# F200s.net
KiCad netlist of a schematic drawn in Altium Designer
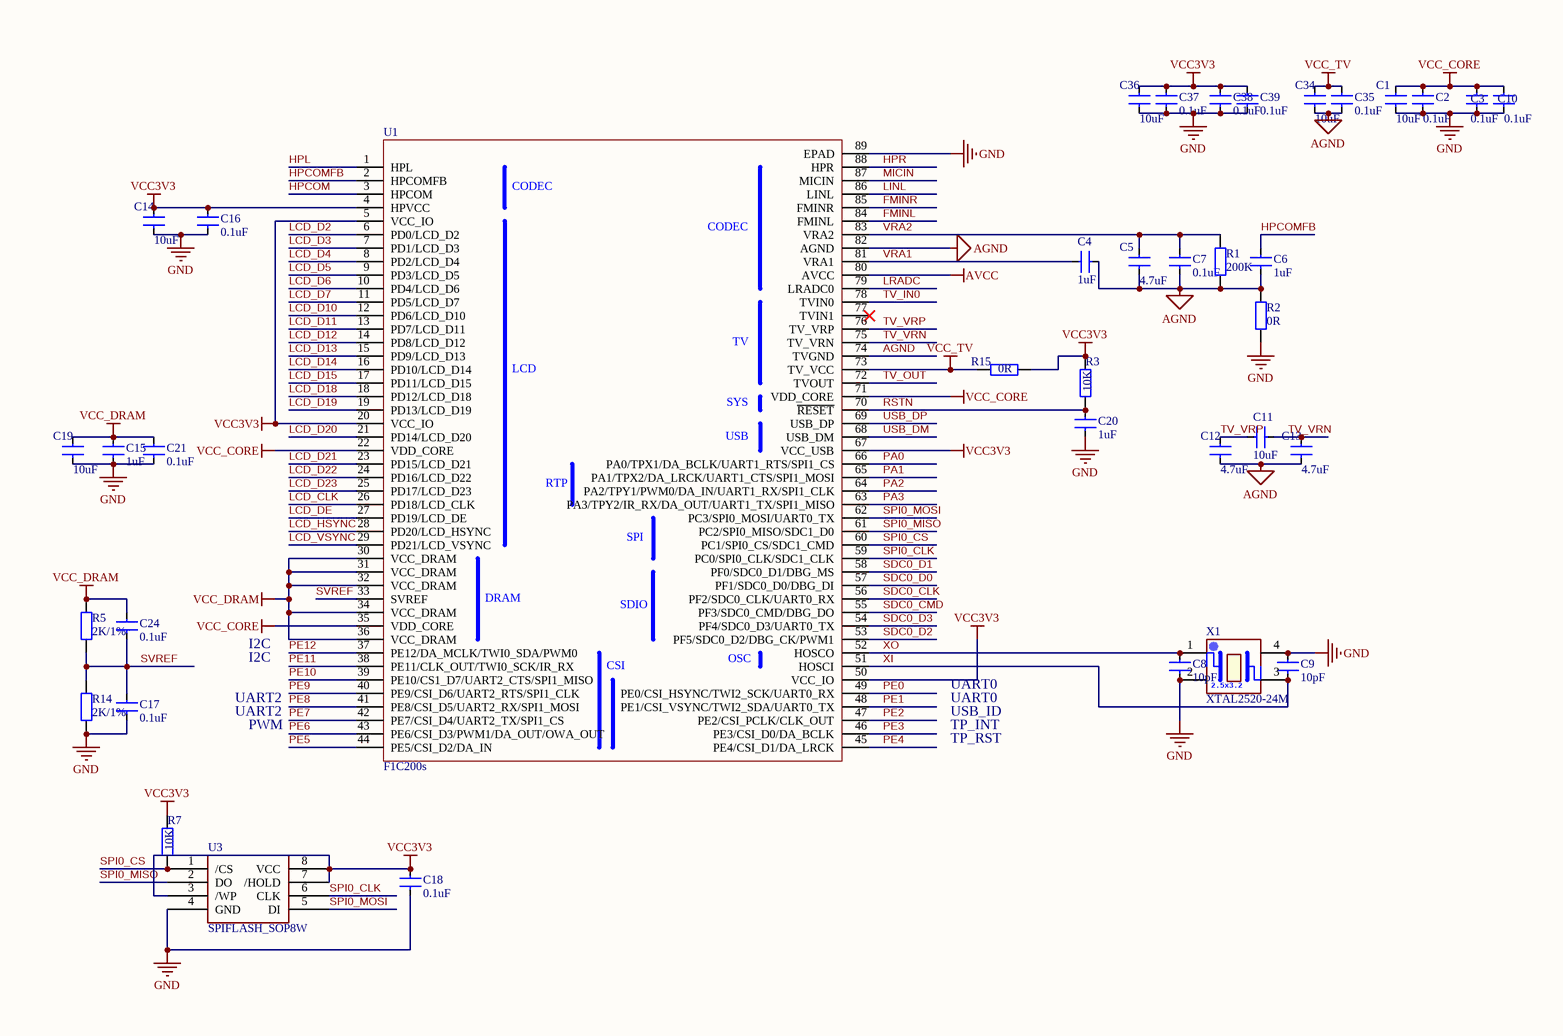
[diagram p0: F200s.SchDoc]

(export (version "E")
  (design (tool "Eeschema 10.0.6"))
  (components
    (comp (ref "C1")
      (value "10uF")
      (footprint "C0402")
      (description "普通小电容")
      (libsource (lib "LIB_MANGO") (part "CAP"))
    )
    (comp (ref "C2")
      (value "0.1uF")
      (footprint "C0402")
      (description "普通小电容")
      (libsource (lib "LIB_MANGO") (part "CAP"))
    )
    (comp (ref "C3")
      (value "0.1uF")
      (footprint "C0402")
      (description "普通小电容")
      (libsource (lib "LIB_MANGO") (part "CAP"))
    )
    (comp (ref "C4")
      (value "1uF")
      (footprint "C0402")
      (description "普通小电容")
      (libsource (lib "LIB_MANGO") (part "CAP"))
    )
    (comp (ref "C5")
      (value "4.7uF")
      (footprint "C0402")
      (description "普通小电容")
      (libsource (lib "LIB_MANGO") (part "CAP"))
    )
    (comp (ref "C6")
      (value "1uF")
      (footprint "C0402")
      (description "普通小电容")
      (libsource (lib "LIB_MANGO") (part "CAP"))
    )
    (comp (ref "C7")
      (value "0.1uF")
      (footprint "C0402")
      (description "普通小电容")
      (libsource (lib "LIB_MANGO") (part "CAP"))
    )
    (comp (ref "C8")
      (value "10pF")
      (footprint "C0402")
      (description "普通小电容")
      (libsource (lib "LIB_MANGO") (part "CAP"))
    )
    (comp (ref "C9")
      (value "10pF")
      (footprint "C0402")
      (description "普通小电容")
      (libsource (lib "LIB_MANGO") (part "CAP"))
    )
    (comp (ref "C10")
      (value "0.1uF")
      (footprint "C0402")
      (description "普通小电容")
      (libsource (lib "LIB_MANGO") (part "CAP"))
    )
    (comp (ref "C11")
      (value "10uF")
      (footprint "C0402")
      (description "普通小电容")
      (libsource (lib "LIB_MANGO") (part "CAP"))
    )
    (comp (ref "C12")
      (value "4.7uF")
      (footprint "C0402")
      (description "普通小电容")
      (libsource (lib "LIB_MANGO") (part "CAP"))
    )
    (comp (ref "C13")
      (value "4.7uF")
      (footprint "C0402")
      (description "普通小电容")
      (libsource (lib "LIB_MANGO") (part "CAP"))
    )
    (comp (ref "C14")
      (value "10uF")
      (footprint "C0402")
      (description "普通小电容")
      (libsource (lib "LIB_MANGO") (part "CAP"))
    )
    (comp (ref "C15")
      (value "1uF")
      (footprint "C0402")
      (description "普通小电容")
      (libsource (lib "LIB_MANGO") (part "CAP"))
    )
    (comp (ref "C16")
      (value "0.1uF")
      (footprint "C0402")
      (description "普通小电容")
      (libsource (lib "LIB_MANGO") (part "CAP"))
    )
    (comp (ref "C17")
      (value "0.1uF")
      (footprint "C0402")
      (description "普通小电容")
      (libsource (lib "LIB_MANGO") (part "CAP"))
    )
    (comp (ref "C18")
      (value "0.1uF")
      (footprint "C0402")
      (description "普通小电容")
      (libsource (lib "LIB_MANGO") (part "CAP"))
    )
    (comp (ref "C19")
      (value "10uF")
      (footprint "C0402")
      (description "普通小电容")
      (libsource (lib "LIB_MANGO") (part "CAP"))
    )
    (comp (ref "C20")
      (value "1uF")
      (footprint "C0402")
      (description "普通小电容")
      (libsource (lib "LIB_MANGO") (part "CAP"))
    )
    (comp (ref "C21")
      (value "0.1uF")
      (footprint "C0402")
      (description "普通小电容")
      (libsource (lib "LIB_MANGO") (part "CAP"))
    )
    (comp (ref "C24")
      (value "0.1uF")
      (footprint "C0402")
      (description "普通小电容")
      (libsource (lib "LIB_MANGO") (part "CAP"))
    )
    (comp (ref "C34")
      (value "10uF")
      (footprint "C0402")
      (description "普通小电容")
      (libsource (lib "LIB_MANGO") (part "CAP"))
    )
    (comp (ref "C35")
      (value "0.1uF")
      (footprint "C0402")
      (description "普通小电容")
      (libsource (lib "LIB_MANGO") (part "CAP"))
    )
    (comp (ref "C36")
      (value "10uF")
      (footprint "C0402")
      (description "普通小电容")
      (libsource (lib "LIB_MANGO") (part "CAP"))
    )
    (comp (ref "C37")
      (value "0.1uF")
      (footprint "C0402")
      (description "普通小电容")
      (libsource (lib "LIB_MANGO") (part "CAP"))
    )
    (comp (ref "C38")
      (value "0.1uF")
      (footprint "C0402")
      (description "普通小电容")
      (libsource (lib "LIB_MANGO") (part "CAP"))
    )
    (comp (ref "C39")
      (value "0.1uF")
      (footprint "C0402")
      (description "普通小电容")
      (libsource (lib "LIB_MANGO") (part "CAP"))
    )
    (comp (ref "R1")
      (value "200K")
      (footprint "R0402")
      (description "普通电阻")
      (libsource (lib "LIB_MANGO") (part "RES"))
    )
    (comp (ref "R2")
      (value "0R")
      (footprint "R0402")
      (description "普通电阻")
      (libsource (lib "LIB_MANGO") (part "RES"))
    )
    (comp (ref "R3")
      (value "10K")
      (footprint "R0402")
      (description "普通电阻")
      (libsource (lib "LIB_MANGO") (part "RES"))
    )
    (comp (ref "R5")
      (value "2K/1%")
      (footprint "R0402")
      (description "普通电阻")
      (libsource (lib "LIB_MANGO") (part "RES"))
    )
    (comp (ref "R7")
      (value "10K")
      (footprint "R0402")
      (description "普通电阻")
      (libsource (lib "LIB_MANGO") (part "RES"))
    )
    (comp (ref "R14")
      (value "2K/1%")
      (footprint "R0402")
      (description "普通电阻")
      (libsource (lib "LIB_MANGO") (part "RES"))
    )
    (comp (ref "R15")
      (value "0R")
      (footprint "R0402")
      (description "普通电阻")
      (libsource (lib "") (part "RES_1"))
    )
    (comp (ref "U1")
      (value "F1C200s")
      (footprint "QFN40P1000X1000X85_HS-89N")
      (libsource (lib "A") (part "F1C200s"))
    )
    (comp (ref "U3")
      (value "SPIFLASH_SOP8W")
      (footprint "WSON-SPIFLASH")
      (libsource (lib "LIB_MANGO") (part "SPIFLASH_SOP8W"))
    )
    (comp (ref "X1")
      (value "XTAL2520-24M")
      (footprint "XTAL2520")
      (libsource (lib "LIB_MANGO") (part "XTAL3225"))
    )
  )
  (nets
    (net (code "1") (name "/FMINL") (class "Default")
      (node (ref "U1") (pin "84") (pinfunction "FMINL_84") (pintype "passive"))
    )
    (net (code "2") (name "/FMINR") (class "Default")
      (node (ref "U1") (pin "85") (pinfunction "FMINR_85") (pintype "passive"))
    )
    (net (code "3") (name "/HPCOM") (class "Default")
      (node (ref "U1") (pin "3") (pinfunction "HPCOM_3") (pintype "passive"))
    )
    (net (code "4") (name "/HPCOMFB") (class "Default")
      (node (ref "C6") (pin "1") (pinfunction "1_1") (pintype "passive"))
      (node (ref "U1") (pin "2") (pinfunction "HPCOMFB_2") (pintype "passive"))
    )
    (net (code "5") (name "/HPL") (class "Default")
      (node (ref "U1") (pin "1") (pinfunction "HPL_1") (pintype "passive"))
    )
    (net (code "6") (name "/HPR") (class "Default")
      (node (ref "U1") (pin "88") (pinfunction "HPR_88") (pintype "passive"))
    )
    (net (code "7") (name "/LCD_CLK") (class "Default")
      (node (ref "U1") (pin "26") (pinfunction "PD18/LCD_CLK_26") (pintype "passive"))
    )
    (net (code "8") (name "/LCD_D2") (class "Default")
      (node (ref "U1") (pin "6") (pinfunction "PD0/LCD_D2_6") (pintype "passive"))
    )
    (net (code "9") (name "/LCD_D3") (class "Default")
      (node (ref "U1") (pin "7") (pinfunction "PD1/LCD_D3_7") (pintype "passive"))
    )
    (net (code "10") (name "/LCD_D4") (class "Default")
      (node (ref "U1") (pin "8") (pinfunction "PD2/LCD_D4_8") (pintype "passive"))
    )
    (net (code "11") (name "/LCD_D5") (class "Default")
      (node (ref "U1") (pin "9") (pinfunction "PD3/LCD_D5_9") (pintype "passive"))
    )
    (net (code "12") (name "/LCD_D6") (class "Default")
      (node (ref "U1") (pin "10") (pinfunction "PD4/LCD_D6_10") (pintype "passive"))
    )
    (net (code "13") (name "/LCD_D7") (class "Default")
      (node (ref "U1") (pin "11") (pinfunction "PD5/LCD_D7_11") (pintype "passive"))
    )
    (net (code "14") (name "/LCD_D10") (class "Default")
      (node (ref "U1") (pin "12") (pinfunction "PD6/LCD_D10_12") (pintype "passive"))
    )
    (net (code "15") (name "/LCD_D11") (class "Default")
      (node (ref "U1") (pin "13") (pinfunction "PD7/LCD_D11_13") (pintype "passive"))
    )
    (net (code "16") (name "/LCD_D12") (class "Default")
      (node (ref "U1") (pin "14") (pinfunction "PD8/LCD_D12_14") (pintype "passive"))
    )
    (net (code "17") (name "/LCD_D13") (class "Default")
      (node (ref "U1") (pin "15") (pinfunction "PD9/LCD_D13_15") (pintype "passive"))
    )
    (net (code "18") (name "/LCD_D14") (class "Default")
      (node (ref "U1") (pin "16") (pinfunction "PD10/LCD_D14_16") (pintype "passive"))
    )
    (net (code "19") (name "/LCD_D15") (class "Default")
      (node (ref "U1") (pin "17") (pinfunction "PD11/LCD_D15_17") (pintype "passive"))
    )
    (net (code "20") (name "/LCD_D18") (class "Default")
      (node (ref "U1") (pin "18") (pinfunction "PD12/LCD_D18_18") (pintype "passive"))
    )
    (net (code "21") (name "/LCD_D19") (class "Default")
      (node (ref "U1") (pin "19") (pinfunction "PD13/LCD_D19_19") (pintype "passive"))
    )
    (net (code "22") (name "/LCD_D20") (class "Default")
      (node (ref "U1") (pin "21") (pinfunction "PD14/LCD_D20_21") (pintype "passive"))
    )
    (net (code "23") (name "/LCD_D21") (class "Default")
      (node (ref "U1") (pin "23") (pinfunction "PD15/LCD_D21_23") (pintype "passive"))
    )
    (net (code "24") (name "/LCD_D22") (class "Default")
      (node (ref "U1") (pin "24") (pinfunction "PD16/LCD_D22_24") (pintype "passive"))
    )
    (net (code "25") (name "/LCD_D23") (class "Default")
      (node (ref "U1") (pin "25") (pinfunction "PD17/LCD_D23_25") (pintype "passive"))
    )
    (net (code "26") (name "/LCD_DE") (class "Default")
      (node (ref "U1") (pin "27") (pinfunction "PD19/LCD_DE_27") (pintype "passive"))
    )
    (net (code "27") (name "/LCD_HSYNC") (class "Default")
      (node (ref "U1") (pin "28") (pinfunction "PD20/LCD_HSYNC_28") (pintype "passive"))
    )
    (net (code "28") (name "/LCD_VSYNC") (class "Default")
      (node (ref "U1") (pin "29") (pinfunction "PD21/LCD_VSYNC_29") (pintype "passive"))
    )
    (net (code "29") (name "/LINL") (class "Default")
      (node (ref "U1") (pin "86") (pinfunction "LINL_86") (pintype "passive"))
    )
    (net (code "30") (name "/LRADC") (class "Default")
      (node (ref "U1") (pin "79") (pinfunction "LRADC0_79") (pintype "passive"))
    )
    (net (code "31") (name "/MICIN") (class "Default")
      (node (ref "U1") (pin "87") (pinfunction "MICIN_87") (pintype "passive"))
    )
    (net (code "32") (name "/PA0") (class "Default")
      (node (ref "U1") (pin "66") (pinfunction "PA0/TPX1/DA_BCLK/UART1_RTS/SPI1_CS_66") (pintype "passive"))
    )
    (net (code "33") (name "/PA1") (class "Default")
      (node (ref "U1") (pin "65") (pinfunction "PA1/TPX2/DA_LRCK/UART1_CTS/SPI1_MOSI_65") (pintype "passive"))
    )
    (net (code "34") (name "/PA2") (class "Default")
      (node (ref "U1") (pin "64") (pinfunction "PA2/TPY1/PWM0/DA_IN/UART1_RX/SPI1_CLK_64") (pintype "passive"))
    )
    (net (code "35") (name "/PA3") (class "Default")
      (node (ref "U1") (pin "63") (pinfunction "PA3/TPY2/IR_RX/DA_OUT/UART1_TX/SPI1_MISO_63") (pintype "passive"))
    )
    (net (code "36") (name "/PE0") (class "Default")
      (node (ref "U1") (pin "49") (pinfunction "PE0/CSI_HSYNC/TWI2_SCK/UART0_RX_49") (pintype "passive"))
    )
    (net (code "37") (name "/PE1") (class "Default")
      (node (ref "U1") (pin "48") (pinfunction "PE1/CSI_VSYNC/TWI2_SDA/UART0_TX_48") (pintype "passive"))
    )
    (net (code "38") (name "/PE2") (class "Default")
      (node (ref "U1") (pin "47") (pinfunction "PE2/CSI_PCLK/CLK_OUT_47") (pintype "passive"))
    )
    (net (code "39") (name "/PE3") (class "Default")
      (node (ref "U1") (pin "46") (pinfunction "PE3/CSI_D0/DA_BCLK_46") (pintype "passive"))
    )
    (net (code "40") (name "/PE4") (class "Default")
      (node (ref "U1") (pin "45") (pinfunction "PE4/CSI_D1/DA_LRCK_45") (pintype "passive"))
    )
    (net (code "41") (name "/PE5") (class "Default")
      (node (ref "U1") (pin "44") (pinfunction "PE5/CSI_D2/DA_IN_44") (pintype "passive"))
    )
    (net (code "42") (name "/PE6") (class "Default")
      (node (ref "U1") (pin "43") (pinfunction "PE6/CSI_D3/PWM1/DA_OUT/OWA_OUT_43") (pintype "passive"))
    )
    (net (code "43") (name "/PE7") (class "Default")
      (node (ref "U1") (pin "42") (pinfunction "PE7/CSI_D4/UART2_TX/SPI1_CS_42") (pintype "passive"))
    )
    (net (code "44") (name "/PE8") (class "Default")
      (node (ref "U1") (pin "41") (pinfunction "PE8/CSI_D5/UART2_RX/SPI1_MOSI_41") (pintype "passive"))
    )
    (net (code "45") (name "/PE9") (class "Default")
      (node (ref "U1") (pin "40") (pinfunction "PE9/CSI_D6/UART2_RTS/SPI1_CLK_40") (pintype "passive"))
    )
    (net (code "46") (name "/PE10") (class "Default")
      (node (ref "U1") (pin "39") (pinfunction "PE10/CS1_D7/UART2_CTS/SPI1_MISO_39") (pintype "passive"))
    )
    (net (code "47") (name "/PE11") (class "Default")
      (node (ref "U1") (pin "38") (pinfunction "PE11/CLK_OUT/TWI0_SCK/IR_RX_38") (pintype "passive"))
    )
    (net (code "48") (name "/PE12") (class "Default")
      (node (ref "U1") (pin "37") (pinfunction "PE12/DA_MCLK/TWI0_SDA/PWM0_37") (pintype "passive"))
    )
    (net (code "49") (name "/RSTN") (class "Default")
      (node (ref "C20") (pin "1") (pinfunction "1_1") (pintype "passive"))
      (node (ref "R3") (pin "1") (pinfunction "1_1") (pintype "passive"))
      (node (ref "U1") (pin "70") (pinfunction "~{RESET}_70") (pintype "passive"))
    )
    (net (code "50") (name "/SDC0_CLK") (class "Default")
      (node (ref "U1") (pin "56") (pinfunction "PF2/SDC0_CLK/UART0_RX_56") (pintype "passive"))
    )
    (net (code "51") (name "/SDC0_CMD") (class "Default")
      (node (ref "U1") (pin "55") (pinfunction "PF3/SDC0_CMD/DBG_DO_55") (pintype "passive"))
    )
    (net (code "52") (name "/SDC0_D0") (class "Default")
      (node (ref "U1") (pin "57") (pinfunction "PF1/SDC0_D0/DBG_DI_57") (pintype "passive"))
    )
    (net (code "53") (name "/SDC0_D1") (class "Default")
      (node (ref "U1") (pin "58") (pinfunction "PF0/SDC0_D1/DBG_MS_58") (pintype "passive"))
    )
    (net (code "54") (name "/SDC0_D2") (class "Default")
      (node (ref "U1") (pin "53") (pinfunction "PF5/SDC0_D2/DBG_CK/PWM1_53") (pintype "passive"))
    )
    (net (code "55") (name "/SDC0_D3") (class "Default")
      (node (ref "U1") (pin "54") (pinfunction "PF4/SDC0_D3/UART0_TX_54") (pintype "passive"))
    )
    (net (code "56") (name "/SPI0_CLK") (class "Default")
      (node (ref "U1") (pin "59") (pinfunction "PC0/SPI0_CLK/SDC1_CLK_59") (pintype "passive"))
      (node (ref "U3") (pin "6") (pinfunction "CLK_6") (pintype "passive"))
    )
    (net (code "57") (name "/SPI0_CS") (class "Default")
      (node (ref "R7") (pin "1") (pinfunction "1_1") (pintype "passive"))
      (node (ref "U1") (pin "60") (pinfunction "PC1/SPI0_CS/SDC1_CMD_60") (pintype "passive"))
      (node (ref "U3") (pin "1") (pinfunction "/CS_1") (pintype "passive"))
    )
    (net (code "58") (name "/SPI0_MISO") (class "Default")
      (node (ref "U1") (pin "61") (pinfunction "PC2/SPI0_MISO/SDC1_D0_61") (pintype "passive"))
      (node (ref "U3") (pin "2") (pinfunction "DO_2") (pintype "passive"))
    )
    (net (code "59") (name "/SPI0_MOSI") (class "Default")
      (node (ref "U1") (pin "62") (pinfunction "PC3/SPI0_MOSI/UART0_TX_62") (pintype "passive"))
      (node (ref "U3") (pin "5") (pinfunction "DI_5") (pintype "passive"))
    )
    (net (code "60") (name "/SVREF") (class "Default")
      (node (ref "C17") (pin "2") (pinfunction "2_2") (pintype "passive"))
      (node (ref "C24") (pin "1") (pinfunction "1_1") (pintype "passive"))
      (node (ref "R14") (pin "2") (pinfunction "2_2") (pintype "passive"))
      (node (ref "R5") (pin "1") (pinfunction "1_1") (pintype "passive"))
      (node (ref "U1") (pin "33") (pinfunction "SVREF_33") (pintype "passive"))
    )
    (net (code "61") (name "/TV_IN0") (class "Default")
      (node (ref "U1") (pin "78") (pinfunction "TVIN0_78") (pintype "passive"))
    )
    (net (code "62") (name "/TV_OUT") (class "Default")
      (node (ref "U1") (pin "72") (pinfunction "TVOUT_72") (pintype "passive"))
    )
    (net (code "63") (name "/TV_VRN") (class "Default")
      (node (ref "C11") (pin "1") (pinfunction "1_1") (pintype "passive"))
      (node (ref "C13") (pin "2") (pinfunction "2_2") (pintype "passive"))
      (node (ref "U1") (pin "75") (pinfunction "TV_VRN_75") (pintype "passive"))
    )
    (net (code "64") (name "/TV_VRP") (class "Default")
      (node (ref "C11") (pin "2") (pinfunction "2_2") (pintype "passive"))
      (node (ref "C12") (pin "2") (pinfunction "2_2") (pintype "passive"))
      (node (ref "U1") (pin "76") (pinfunction "TV_VRP_76") (pintype "passive"))
    )
    (net (code "65") (name "/USB_DM") (class "Default")
      (node (ref "U1") (pin "68") (pinfunction "USB_DM_68") (pintype "passive"))
    )
    (net (code "66") (name "/USB_DP") (class "Default")
      (node (ref "U1") (pin "69") (pinfunction "USB_DP_69") (pintype "passive"))
    )
    (net (code "67") (name "/VRA1") (class "Default")
      (node (ref "C4") (pin "1") (pinfunction "1_1") (pintype "passive"))
      (node (ref "U1") (pin "81") (pinfunction "VRA1_81") (pintype "passive"))
    )
    (net (code "68") (name "/VRA2") (class "Default")
      (node (ref "C5") (pin "2") (pinfunction "2_2") (pintype "passive"))
      (node (ref "C7") (pin "2") (pinfunction "2_2") (pintype "passive"))
      (node (ref "R1") (pin "2") (pinfunction "2_2") (pintype "passive"))
      (node (ref "U1") (pin "83") (pinfunction "VRA2_83") (pintype "passive"))
    )
    (net (code "69") (name "/XI") (class "Default")
      (node (ref "C9") (pin "1") (pinfunction "1_1") (pintype "passive"))
      (node (ref "U1") (pin "51") (pinfunction "HOSCI_51") (pintype "passive"))
      (node (ref "X1") (pin "3") (pinfunction "X2_3") (pintype "passive"))
    )
    (net (code "70") (name "/XO") (class "Default")
      (node (ref "C8") (pin "2") (pinfunction "2_2") (pintype "passive"))
      (node (ref "U1") (pin "52") (pinfunction "HOSCO_52") (pintype "passive"))
      (node (ref "X1") (pin "1") (pinfunction "X1_1") (pintype "passive"))
    )
    (net (code "71") (name "AGND") (class "Default")
      (node (ref "C12") (pin "1") (pinfunction "1_1") (pintype "passive"))
      (node (ref "C13") (pin "1") (pinfunction "1_1") (pintype "passive"))
      (node (ref "C34") (pin "1") (pinfunction "1_1") (pintype "passive"))
      (node (ref "C35") (pin "1") (pinfunction "1_1") (pintype "passive"))
      (node (ref "C4") (pin "2") (pinfunction "2_2") (pintype "passive"))
      (node (ref "C5") (pin "1") (pinfunction "1_1") (pintype "passive"))
      (node (ref "C6") (pin "2") (pinfunction "2_2") (pintype "passive"))
      (node (ref "C7") (pin "1") (pinfunction "1_1") (pintype "passive"))
      (node (ref "R1") (pin "1") (pinfunction "1_1") (pintype "passive"))
      (node (ref "R2") (pin "2") (pinfunction "2_2") (pintype "passive"))
      (node (ref "U1") (pin "74") (pinfunction "TVGND_74") (pintype "passive"))
      (node (ref "U1") (pin "82") (pinfunction "AGND_82") (pintype "passive"))
    )
    (net (code "72") (name "AVCC") (class "Default")
      (node (ref "U1") (pin "80") (pinfunction "AVCC_80") (pintype "passive"))
    )
    (net (code "73") (name "GND") (class "Default")
      (node (ref "C1") (pin "1") (pinfunction "1_1") (pintype "passive"))
      (node (ref "C10") (pin "1") (pinfunction "1_1") (pintype "passive"))
      (node (ref "C14") (pin "1") (pinfunction "1_1") (pintype "passive"))
      (node (ref "C15") (pin "1") (pinfunction "1_1") (pintype "passive"))
      (node (ref "C16") (pin "1") (pinfunction "1_1") (pintype "passive"))
      (node (ref "C17") (pin "1") (pinfunction "1_1") (pintype "passive"))
      (node (ref "C18") (pin "1") (pinfunction "1_1") (pintype "passive"))
      (node (ref "C19") (pin "1") (pinfunction "1_1") (pintype "passive"))
      (node (ref "C2") (pin "1") (pinfunction "1_1") (pintype "passive"))
      (node (ref "C20") (pin "2") (pinfunction "2_2") (pintype "passive"))
      (node (ref "C21") (pin "1") (pinfunction "1_1") (pintype "passive"))
      (node (ref "C3") (pin "1") (pinfunction "1_1") (pintype "passive"))
      (node (ref "C36") (pin "1") (pinfunction "1_1") (pintype "passive"))
      (node (ref "C37") (pin "1") (pinfunction "1_1") (pintype "passive"))
      (node (ref "C38") (pin "1") (pinfunction "1_1") (pintype "passive"))
      (node (ref "C39") (pin "1") (pinfunction "1_1") (pintype "passive"))
      (node (ref "C8") (pin "1") (pinfunction "1_1") (pintype "passive"))
      (node (ref "C9") (pin "2") (pinfunction "2_2") (pintype "passive"))
      (node (ref "R14") (pin "1") (pinfunction "1_1") (pintype "passive"))
      (node (ref "R2") (pin "1") (pinfunction "1_1") (pintype "passive"))
      (node (ref "U1") (pin "89") (pinfunction "EPAD_89") (pintype "passive"))
      (node (ref "U3") (pin "4") (pinfunction "GND_4") (pintype "passive"))
      (node (ref "X1") (pin "2") (pinfunction "NC1_2") (pintype "passive"))
      (node (ref "X1") (pin "4") (pinfunction "NC2_4") (pintype "passive"))
    )
    (net (code "74") (name "VCC3V3") (class "Default")
      (node (ref "C14") (pin "2") (pinfunction "2_2") (pintype "passive"))
      (node (ref "C16") (pin "2") (pinfunction "2_2") (pintype "passive"))
      (node (ref "C18") (pin "2") (pinfunction "2_2") (pintype "passive"))
      (node (ref "C36") (pin "2") (pinfunction "2_2") (pintype "passive"))
      (node (ref "C37") (pin "2") (pinfunction "2_2") (pintype "passive"))
      (node (ref "C38") (pin "2") (pinfunction "2_2") (pintype "passive"))
      (node (ref "C39") (pin "2") (pinfunction "2_2") (pintype "passive"))
      (node (ref "R15") (pin "1") (pinfunction "1_1") (pintype "passive"))
      (node (ref "R3") (pin "2") (pinfunction "2_2") (pintype "passive"))
      (node (ref "R7") (pin "2") (pinfunction "2_2") (pintype "passive"))
      (node (ref "U1") (pin "20") (pinfunction "VCC_IO_20") (pintype "passive"))
      (node (ref "U1") (pin "4") (pinfunction "HPVCC_4") (pintype "passive"))
      (node (ref "U1") (pin "5") (pinfunction "VCC_IO_5") (pintype "passive"))
      (node (ref "U1") (pin "50") (pinfunction "VCC_IO_50") (pintype "passive"))
      (node (ref "U1") (pin "67") (pinfunction "VCC_USB_67") (pintype "passive"))
      (node (ref "U3") (pin "3") (pinfunction "/WP_3") (pintype "passive"))
      (node (ref "U3") (pin "7") (pinfunction "/HOLD_7") (pintype "passive"))
      (node (ref "U3") (pin "8") (pinfunction "VCC_8") (pintype "passive"))
    )
    (net (code "75") (name "VCC_CORE") (class "Default")
      (node (ref "C1") (pin "2") (pinfunction "2_2") (pintype "passive"))
      (node (ref "C10") (pin "2") (pinfunction "2_2") (pintype "passive"))
      (node (ref "C2") (pin "2") (pinfunction "2_2") (pintype "passive"))
      (node (ref "C3") (pin "2") (pinfunction "2_2") (pintype "passive"))
      (node (ref "U1") (pin "22") (pinfunction "VDD_CORE_22") (pintype "passive"))
      (node (ref "U1") (pin "35") (pinfunction "VDD_CORE_35") (pintype "passive"))
      (node (ref "U1") (pin "71") (pinfunction "VDD_CORE_71") (pintype "passive"))
    )
    (net (code "76") (name "VCC_DRAM") (class "Default")
      (node (ref "C15") (pin "2") (pinfunction "2_2") (pintype "passive"))
      (node (ref "C19") (pin "2") (pinfunction "2_2") (pintype "passive"))
      (node (ref "C21") (pin "2") (pinfunction "2_2") (pintype "passive"))
      (node (ref "C24") (pin "2") (pinfunction "2_2") (pintype "passive"))
      (node (ref "R5") (pin "2") (pinfunction "2_2") (pintype "passive"))
      (node (ref "U1") (pin "30") (pinfunction "VCC_DRAM_30") (pintype "passive"))
      (node (ref "U1") (pin "31") (pinfunction "VCC_DRAM_31") (pintype "passive"))
      (node (ref "U1") (pin "32") (pinfunction "VCC_DRAM_32") (pintype "passive"))
      (node (ref "U1") (pin "34") (pinfunction "VCC_DRAM_34") (pintype "passive"))
      (node (ref "U1") (pin "36") (pinfunction "VCC_DRAM_36") (pintype "passive"))
    )
    (net (code "77") (name "VCC_TV") (class "Default")
      (node (ref "C34") (pin "2") (pinfunction "2_2") (pintype "passive"))
      (node (ref "C35") (pin "2") (pinfunction "2_2") (pintype "passive"))
      (node (ref "R15") (pin "2") (pinfunction "2_2") (pintype "passive"))
      (node (ref "U1") (pin "73") (pinfunction "TV_VCC_73") (pintype "passive"))
    )
    (net (code "78") (name "unconnected-(U1-TVIN1-Pad77)") (class "Default")
      (node (ref "U1") (pin "77") (pinfunction "TVIN1_77") (pintype "passive+no_connect"))
    )
  )
)
